# uc.net
KiCad netlist of a schematic drawn in Altium Designer
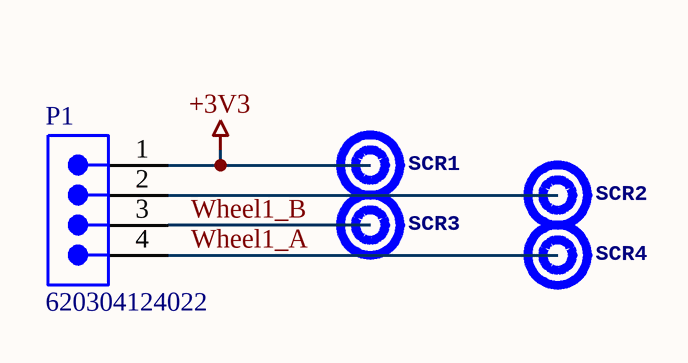
[diagram p0: uc.SchDoc]

(export (version "E")
  (design (tool "Eeschema 10.0.6"))
  (components
    (comp (ref "P1")
      (value "620304124022")
      (footprint "620304124022")
      (libsource (lib "Altium Content Vault") (part "Header_Male_1R_04P"))
    )
    (comp (ref "SCR1")
      (value "SCREW-PTH_M3")
      (footprint "SCREW-TCHC-M3-PTH")
      (fields (field (name "MF") "GENERIC"))
      (libsource (lib "screw-eno") (part "SCREW-PTH_M3"))
    )
    (comp (ref "SCR2")
      (value "SCREW-PTH_M3")
      (footprint "SCREW-TCHC-M3-PTH")
      (fields (field (name "MF") "GENERIC"))
      (libsource (lib "screw-eno") (part "SCREW-PTH_M3"))
    )
    (comp (ref "SCR3")
      (value "SCREW-PTH_M3")
      (footprint "SCREW-TCHC-M3-PTH")
      (fields (field (name "MF") "GENERIC"))
      (libsource (lib "screw-eno") (part "SCREW-PTH_M3"))
    )
    (comp (ref "SCR4")
      (value "SCREW-PTH_M3")
      (footprint "SCREW-TCHC-M3-PTH")
      (fields (field (name "MF") "GENERIC"))
      (libsource (lib "screw-eno") (part "SCREW-PTH_M3"))
    )
  )
  (nets
    (net (code "1") (name "+3V3") (class "Default")
      (node (ref "P1") (pin "1") (pinfunction "1_1") (pintype "passive"))
      (node (ref "SCR1") (pin "1") (pinfunction "1_1") (pintype "passive"))
    )
    (net (code "2") (name "/Wheel1_A") (class "Default")
      (node (ref "P1") (pin "4") (pinfunction "4_4") (pintype "passive"))
      (node (ref "SCR4") (pin "1") (pinfunction "1_1") (pintype "passive"))
    )
    (net (code "3") (name "/Wheel1_B") (class "Default")
      (node (ref "P1") (pin "3") (pinfunction "3_3") (pintype "passive"))
      (node (ref "SCR3") (pin "1") (pinfunction "1_1") (pintype "passive"))
    )
    (net (code "4") (name "Net-(P1-Pad2)") (class "Default")
      (node (ref "P1") (pin "2") (pinfunction "2_2") (pintype "passive"))
      (node (ref "SCR2") (pin "1") (pinfunction "1_1") (pintype "passive"))
    )
  )
)
